# tang1.net
KiCad netlist of a schematic drawn in Altium Designer
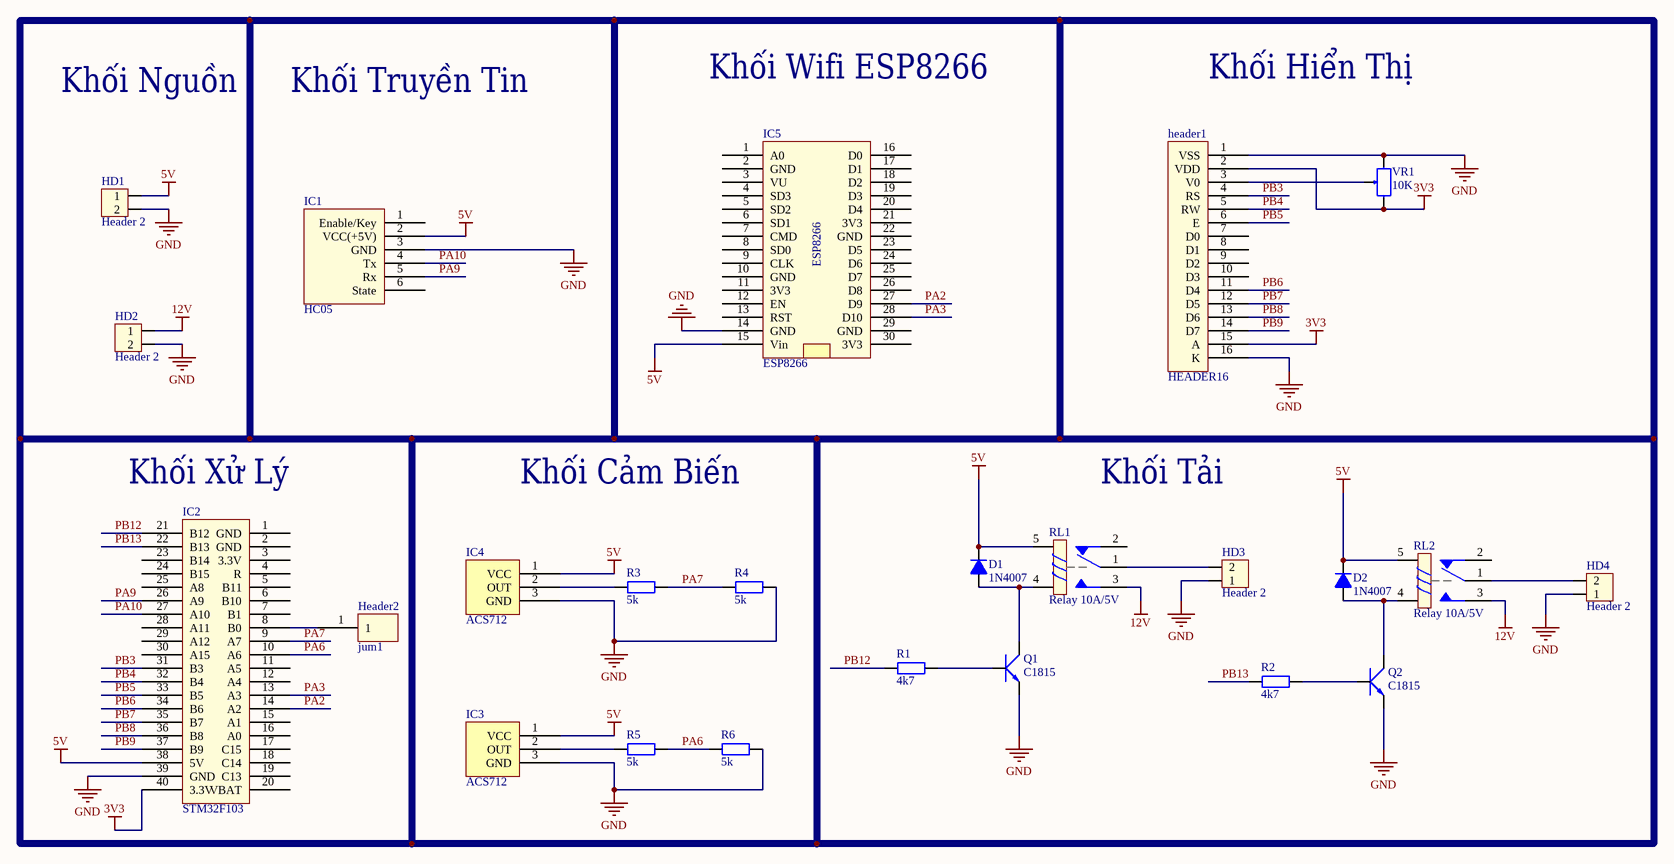
[diagram p0: tang1.SchDoc]

(export (version "E")
  (design (tool "Eeschema 10.0.6"))
  (components
    (comp (ref "D1")
      (value "1N4007")
      (footprint "D1A")
      (description "Diode 1A")
      (libsource (lib "syhaunguyen") (part "D1A"))
    )
    (comp (ref "D2")
      (value "1N4007")
      (footprint "D1A")
      (description "Diode 1A")
      (libsource (lib "syhaunguyen") (part "D1A"))
    )
    (comp (ref "HD1")
      (value "Header 2")
      (footprint "HED2")
      (description "Header 2 (Green)")
      (libsource (lib "") (part "Hed2_1"))
    )
    (comp (ref "HD2")
      (value "Header 2")
      (footprint "HED2")
      (description "Header 2 (Green)")
      (libsource (lib "") (part "Hed2_1"))
    )
    (comp (ref "HD3")
      (value "Header 2")
      (footprint "HED2")
      (description "Header 2 (Green)")
      (libsource (lib "syhaunguyen") (part "Hed2"))
    )
    (comp (ref "HD4")
      (value "Header 2")
      (footprint "HED2")
      (description "Header 2 (Green)")
      (libsource (lib "syhaunguyen") (part "Hed2"))
    )
    (comp (ref "header1")
      (value "HEADER16")
      (footprint "header16_pin")
      (libsource (lib "header16") (part "HEADER16"))
    )
    (comp (ref "Header2") (value "jum1") (footprint "PCBComponent_1") (libsource (lib "jum1") (part "jum1")))
    (comp (ref "IC1") (value "HC05") (footprint "HC05_Pin") (libsource (lib "hc05") (part "HC05")))
    (comp (ref "IC2")
      (value "STM32F103")
      (footprint "STM32")
      (libsource (lib "STM32F103") (part "STM32F103"))
    )
    (comp (ref "IC3")
      (value "ACS712")
      (footprint "ACS712:PCBComponent_1")
      (libsource (lib "ACS712") (part "ACS712"))
    )
    (comp (ref "IC4")
      (value "ACS712")
      (footprint "ACS712:PCBComponent_1")
      (libsource (lib "ACS712") (part "ACS712"))
    )
    (comp (ref "IC5")
      (value "ESP8266")
      (footprint "ESP8266 V2")
      (libsource (lib "ESP8266_V2") (part "ESP8266_V2"))
    )
    (comp (ref "Q1")
      (value "C1815")
      (footprint "QTO-92")
      (description "NPN 600mW, ECB")
      (libsource (lib "syhaunguyen") (part "C1815"))
    )
    (comp (ref "Q2")
      (value "C1815")
      (footprint "QTO-92")
      (description "NPN 600mW, ECB")
      (libsource (lib "syhaunguyen") (part "C1815"))
    )
    (comp (ref "R1")
      (value "4k7")
      (footprint "R1/4W")
      (description "Resistor 1/4W")
      (libsource (lib "syhaunguyen") (part "R1/4W"))
    )
    (comp (ref "R2")
      (value "4k7")
      (footprint "R1/4W")
      (description "Resistor 1/4W")
      (libsource (lib "syhaunguyen") (part "R1/4W"))
    )
    (comp (ref "R3")
      (value "5k")
      (footprint "R1/4W")
      (description "Resistor 1/4W")
      (libsource (lib "syhaunguyen") (part "R1/4W"))
    )
    (comp (ref "R4")
      (value "5k")
      (footprint "R1/4W")
      (description "Resistor 1/4W")
      (libsource (lib "syhaunguyen") (part "R1/4W"))
    )
    (comp (ref "R5")
      (value "5k")
      (footprint "R1/4W")
      (description "Resistor 1/4W")
      (libsource (lib "syhaunguyen") (part "R1/4W"))
    )
    (comp (ref "R6")
      (value "5k")
      (footprint "R1/4W")
      (description "Resistor 1/4W")
      (libsource (lib "syhaunguyen") (part "R1/4W"))
    )
    (comp (ref "RL1")
      (value "Relay 10A/5V")
      (footprint "RL_SPDT_10A")
      (description "Relay SPDT,10A - 12VDC 5 Pin")
      (libsource (lib "syhaunguyen") (part "Relay 1"))
    )
    (comp (ref "RL2")
      (value "Relay 10A/5V")
      (footprint "RL_SPDT_10A")
      (description "Relay SPDT,10A - 12VDC 5 Pin")
      (libsource (lib "syhaunguyen") (part "Relay 1"))
    )
    (comp (ref "VR1")
      (value "10K")
      (footprint "VR")
      (description "Var Resistor")
      (libsource (lib "syhaunguyen") (part "VR"))
    )
  )
  (nets
    (net (code "1") (name "/PA2") (class "Default")
      (node (ref "IC2") (pin "14") (pinfunction "A2_14") (pintype "passive"))
      (node (ref "IC5") (pin "27") (pinfunction "D9_27") (pintype "passive"))
    )
    (net (code "2") (name "/PA3") (class "Default")
      (node (ref "IC2") (pin "13") (pinfunction "A3_13") (pintype "passive"))
      (node (ref "IC5") (pin "28") (pinfunction "D10_28") (pintype "passive"))
    )
    (net (code "3") (name "/PA6") (class "Default")
      (node (ref "IC2") (pin "10") (pinfunction "A6_10") (pintype "passive"))
      (node (ref "R5") (pin "2") (pinfunction "2_2") (pintype "passive"))
      (node (ref "R6") (pin "1") (pinfunction "1_1") (pintype "passive"))
    )
    (net (code "4") (name "/PA7") (class "Default")
      (node (ref "IC2") (pin "9") (pinfunction "A7_9") (pintype "passive"))
      (node (ref "R3") (pin "2") (pinfunction "2_2") (pintype "passive"))
      (node (ref "R4") (pin "1") (pinfunction "1_1") (pintype "passive"))
    )
    (net (code "5") (name "/PA9") (class "Default")
      (node (ref "IC1") (pin "5") (pinfunction "Rx_5") (pintype "passive"))
      (node (ref "IC2") (pin "26") (pinfunction "A9_26") (pintype "passive"))
    )
    (net (code "6") (name "/PA10") (class "Default")
      (node (ref "IC1") (pin "4") (pinfunction "Tx_4") (pintype "passive"))
      (node (ref "IC2") (pin "27") (pinfunction "A10_27") (pintype "passive"))
    )
    (net (code "7") (name "/PB3") (class "Default")
      (node (ref "IC2") (pin "31") (pinfunction "B3_31") (pintype "passive"))
      (node (ref "header1") (pin "4") (pinfunction "RS_4") (pintype "passive"))
    )
    (net (code "8") (name "/PB4") (class "Default")
      (node (ref "IC2") (pin "32") (pinfunction "B4_32") (pintype "passive"))
      (node (ref "header1") (pin "5") (pinfunction "RW_5") (pintype "passive"))
    )
    (net (code "9") (name "/PB5") (class "Default")
      (node (ref "IC2") (pin "33") (pinfunction "B5_33") (pintype "passive"))
      (node (ref "header1") (pin "6") (pinfunction "E_6") (pintype "passive"))
    )
    (net (code "10") (name "/PB6") (class "Default")
      (node (ref "IC2") (pin "34") (pinfunction "B6_34") (pintype "passive"))
      (node (ref "header1") (pin "11") (pinfunction "D4_11") (pintype "passive"))
    )
    (net (code "11") (name "/PB7") (class "Default")
      (node (ref "IC2") (pin "35") (pinfunction "B7_35") (pintype "passive"))
      (node (ref "header1") (pin "12") (pinfunction "D5_12") (pintype "passive"))
    )
    (net (code "12") (name "/PB8") (class "Default")
      (node (ref "IC2") (pin "36") (pinfunction "B8_36") (pintype "passive"))
      (node (ref "header1") (pin "13") (pinfunction "D6_13") (pintype "passive"))
    )
    (net (code "13") (name "/PB9") (class "Default")
      (node (ref "IC2") (pin "37") (pinfunction "B9_37") (pintype "passive"))
      (node (ref "header1") (pin "14") (pinfunction "D7_14") (pintype "passive"))
    )
    (net (code "14") (name "/PB12") (class "Default")
      (node (ref "IC2") (pin "21") (pinfunction "B12_21") (pintype "passive"))
      (node (ref "R1") (pin "1") (pinfunction "1_1") (pintype "passive"))
    )
    (net (code "15") (name "/PB13") (class "Default")
      (node (ref "IC2") (pin "22") (pinfunction "B13_22") (pintype "passive"))
      (node (ref "R2") (pin "1") (pinfunction "1_1") (pintype "passive"))
    )
    (net (code "16") (name "3V3") (class "Default")
      (node (ref "IC2") (pin "40") (pinfunction "3.3V_40") (pintype "passive"))
      (node (ref "VR1") (pin "1") (pinfunction "1_1") (pintype "passive"))
      (node (ref "header1") (pin "15") (pinfunction "A_15") (pintype "passive"))
      (node (ref "header1") (pin "2") (pinfunction "VDD_2") (pintype "passive"))
    )
    (net (code "17") (name "5V") (class "Default")
      (node (ref "D1") (pin "2") (pinfunction "K_2") (pintype "passive"))
      (node (ref "D2") (pin "2") (pinfunction "K_2") (pintype "passive"))
      (node (ref "HD1") (pin "1") (pinfunction "1_1") (pintype "passive"))
      (node (ref "IC1") (pin "2") (pinfunction "VCC(+5V)_2") (pintype "passive"))
      (node (ref "IC2") (pin "38") (pinfunction "5V_38") (pintype "passive"))
      (node (ref "IC3") (pin "1") (pinfunction "VCC_1") (pintype "passive"))
      (node (ref "IC4") (pin "1") (pinfunction "VCC_1") (pintype "passive"))
      (node (ref "IC5") (pin "15") (pinfunction "Vin_15") (pintype "passive"))
      (node (ref "RL1") (pin "5") (pinfunction "5_5") (pintype "passive"))
      (node (ref "RL2") (pin "5") (pinfunction "5_5") (pintype "passive"))
    )
    (net (code "18") (name "12V") (class "Default")
      (node (ref "HD2") (pin "1") (pinfunction "1_1") (pintype "passive"))
      (node (ref "RL1") (pin "3") (pinfunction "3_3") (pintype "passive"))
      (node (ref "RL2") (pin "3") (pinfunction "3_3") (pintype "passive"))
    )
    (net (code "19") (name "GND") (class "Default")
      (node (ref "HD1") (pin "2") (pinfunction "2_2") (pintype "passive"))
      (node (ref "HD2") (pin "2") (pinfunction "2_2") (pintype "passive"))
      (node (ref "HD3") (pin "1") (pinfunction "1_1") (pintype "passive"))
      (node (ref "HD4") (pin "1") (pinfunction "1_1") (pintype "passive"))
      (node (ref "IC1") (pin "3") (pinfunction "GND_3") (pintype "passive"))
      (node (ref "IC2") (pin "39") (pinfunction "GND_39") (pintype "passive"))
      (node (ref "IC3") (pin "3") (pinfunction "GND_3") (pintype "passive"))
      (node (ref "IC4") (pin "3") (pinfunction "GND_3") (pintype "passive"))
      (node (ref "IC5") (pin "14") (pinfunction "GND_14") (pintype "passive"))
      (node (ref "Q1") (pin "1") (pinfunction "E_1") (pintype "passive"))
      (node (ref "Q2") (pin "1") (pinfunction "E_1") (pintype "passive"))
      (node (ref "R4") (pin "2") (pinfunction "2_2") (pintype "passive"))
      (node (ref "R6") (pin "2") (pinfunction "2_2") (pintype "passive"))
      (node (ref "VR1") (pin "3") (pinfunction "3_3") (pintype "passive"))
      (node (ref "header1") (pin "1") (pinfunction "VSS_1") (pintype "passive"))
      (node (ref "header1") (pin "16") (pinfunction "K_16") (pintype "passive"))
    )
    (net (code "20") (name "Net-(D1-A)") (class "Default")
      (node (ref "D1") (pin "1") (pinfunction "A_1") (pintype "passive"))
      (node (ref "Q1") (pin "2") (pinfunction "C_2") (pintype "passive"))
      (node (ref "RL1") (pin "4") (pinfunction "4_4") (pintype "passive"))
    )
    (net (code "21") (name "Net-(D2-A)") (class "Default")
      (node (ref "D2") (pin "1") (pinfunction "A_1") (pintype "passive"))
      (node (ref "Q2") (pin "2") (pinfunction "C_2") (pintype "passive"))
      (node (ref "RL2") (pin "4") (pinfunction "4_4") (pintype "passive"))
    )
    (net (code "22") (name "Net-(HD3-Pad2)") (class "Default")
      (node (ref "HD3") (pin "2") (pinfunction "2_2") (pintype "passive"))
      (node (ref "RL1") (pin "1") (pinfunction "1_1") (pintype "passive"))
    )
    (net (code "23") (name "Net-(HD4-Pad2)") (class "Default")
      (node (ref "HD4") (pin "2") (pinfunction "2_2") (pintype "passive"))
      (node (ref "RL2") (pin "1") (pinfunction "1_1") (pintype "passive"))
    )
    (net (code "24") (name "Net-(IC2-B0)") (class "Default")
      (node (ref "Header2") (pin "1") (pinfunction "1_1") (pintype "passive"))
      (node (ref "IC2") (pin "8") (pinfunction "B0_8") (pintype "passive"))
    )
    (net (code "25") (name "Net-(IC3-OUT)") (class "Default")
      (node (ref "IC3") (pin "2") (pinfunction "OUT_2") (pintype "passive"))
      (node (ref "R5") (pin "1") (pinfunction "1_1") (pintype "passive"))
    )
    (net (code "26") (name "Net-(IC4-OUT)") (class "Default")
      (node (ref "IC4") (pin "2") (pinfunction "OUT_2") (pintype "passive"))
      (node (ref "R3") (pin "1") (pinfunction "1_1") (pintype "passive"))
    )
    (net (code "27") (name "Net-(Q1-B)") (class "Default")
      (node (ref "Q1") (pin "3") (pinfunction "B_3") (pintype "passive"))
      (node (ref "R1") (pin "2") (pinfunction "2_2") (pintype "passive"))
    )
    (net (code "28") (name "Net-(Q2-B)") (class "Default")
      (node (ref "Q2") (pin "3") (pinfunction "B_3") (pintype "passive"))
      (node (ref "R2") (pin "2") (pinfunction "2_2") (pintype "passive"))
    )
    (net (code "29") (name "Net-(header1-V0)") (class "Default")
      (node (ref "VR1") (pin "2") (pinfunction "2_2") (pintype "passive"))
      (node (ref "header1") (pin "3") (pinfunction "V0_3") (pintype "passive"))
    )
    (net (code "30") (name "unconnected-(IC1-Enable{slash}Key-Pad1)") (class "Default")
      (node (ref "IC1") (pin "1") (pinfunction "Enable/Key_1") (pintype "passive"))
    )
    (net (code "31") (name "unconnected-(IC1-State-Pad6)") (class "Default")
      (node (ref "IC1") (pin "6") (pinfunction "State_6") (pintype "passive"))
    )
    (net (code "32") (name "unconnected-(IC2-3.3V-Pad3)") (class "Default")
      (node (ref "IC2") (pin "3") (pinfunction "3.3V_3") (pintype "passive"))
    )
    (net (code "33") (name "unconnected-(IC2-A0-Pad16)") (class "Default")
      (node (ref "IC2") (pin "16") (pinfunction "A0_16") (pintype "passive"))
    )
    (net (code "34") (name "unconnected-(IC2-A1-Pad15)") (class "Default")
      (node (ref "IC2") (pin "15") (pinfunction "A1_15") (pintype "passive"))
    )
    (net (code "35") (name "unconnected-(IC2-A4-Pad12)") (class "Default")
      (node (ref "IC2") (pin "12") (pinfunction "A4_12") (pintype "passive"))
    )
    (net (code "36") (name "unconnected-(IC2-A5-Pad11)") (class "Default")
      (node (ref "IC2") (pin "11") (pinfunction "A5_11") (pintype "passive"))
    )
    (net (code "37") (name "unconnected-(IC2-A8-Pad25)") (class "Default")
      (node (ref "IC2") (pin "25") (pinfunction "A8_25") (pintype "passive"))
    )
    (net (code "38") (name "unconnected-(IC2-A11-Pad28)") (class "Default")
      (node (ref "IC2") (pin "28") (pinfunction "A11_28") (pintype "passive"))
    )
    (net (code "39") (name "unconnected-(IC2-A12-Pad29)") (class "Default")
      (node (ref "IC2") (pin "29") (pinfunction "A12_29") (pintype "passive"))
    )
    (net (code "40") (name "unconnected-(IC2-A15-Pad30)") (class "Default")
      (node (ref "IC2") (pin "30") (pinfunction "A15_30") (pintype "passive"))
    )
    (net (code "41") (name "unconnected-(IC2-B1-Pad7)") (class "Default")
      (node (ref "IC2") (pin "7") (pinfunction "B1_7") (pintype "passive"))
    )
    (net (code "42") (name "unconnected-(IC2-B10-Pad6)") (class "Default")
      (node (ref "IC2") (pin "6") (pinfunction "B10_6") (pintype "passive"))
    )
    (net (code "43") (name "unconnected-(IC2-B11-Pad5)") (class "Default")
      (node (ref "IC2") (pin "5") (pinfunction "B11_5") (pintype "passive"))
    )
    (net (code "44") (name "unconnected-(IC2-B14-Pad23)") (class "Default")
      (node (ref "IC2") (pin "23") (pinfunction "B14_23") (pintype "passive"))
    )
    (net (code "45") (name "unconnected-(IC2-B15-Pad24)") (class "Default")
      (node (ref "IC2") (pin "24") (pinfunction "B15_24") (pintype "passive"))
    )
    (net (code "46") (name "unconnected-(IC2-C13-Pad19)") (class "Default")
      (node (ref "IC2") (pin "19") (pinfunction "C13_19") (pintype "passive"))
    )
    (net (code "47") (name "unconnected-(IC2-C14-Pad18)") (class "Default")
      (node (ref "IC2") (pin "18") (pinfunction "C14_18") (pintype "passive"))
    )
    (net (code "48") (name "unconnected-(IC2-C15-Pad17)") (class "Default")
      (node (ref "IC2") (pin "17") (pinfunction "C15_17") (pintype "passive"))
    )
    (net (code "49") (name "unconnected-(IC2-GND-Pad1)") (class "Default")
      (node (ref "IC2") (pin "1") (pinfunction "GND_1") (pintype "passive"))
    )
    (net (code "50") (name "unconnected-(IC2-GND-Pad2)") (class "Default")
      (node (ref "IC2") (pin "2") (pinfunction "GND_2") (pintype "passive"))
    )
    (net (code "51") (name "unconnected-(IC2-R-Pad4)") (class "Default")
      (node (ref "IC2") (pin "4") (pinfunction "R_4") (pintype "passive"))
    )
    (net (code "52") (name "unconnected-(IC2-VBAT-Pad20)") (class "Default")
      (node (ref "IC2") (pin "20") (pinfunction "VBAT_20") (pintype "passive"))
    )
    (net (code "53") (name "unconnected-(IC5-3V3-Pad11)") (class "Default")
      (node (ref "IC5") (pin "11") (pinfunction "3V3_11") (pintype "passive"))
    )
    (net (code "54") (name "unconnected-(IC5-3V3-Pad21)") (class "Default")
      (node (ref "IC5") (pin "21") (pinfunction "3V3_21") (pintype "passive"))
    )
    (net (code "55") (name "unconnected-(IC5-3V3-Pad30)") (class "Default")
      (node (ref "IC5") (pin "30") (pinfunction "3V3_30") (pintype "passive"))
    )
    (net (code "56") (name "unconnected-(IC5-A0-Pad1)") (class "Default")
      (node (ref "IC5") (pin "1") (pinfunction "A0_1") (pintype "passive"))
    )
    (net (code "57") (name "unconnected-(IC5-CLK-Pad9)") (class "Default")
      (node (ref "IC5") (pin "9") (pinfunction "CLK_9") (pintype "passive"))
    )
    (net (code "58") (name "unconnected-(IC5-CMD-Pad7)") (class "Default")
      (node (ref "IC5") (pin "7") (pinfunction "CMD_7") (pintype "passive"))
    )
    (net (code "59") (name "unconnected-(IC5-D0-Pad16)") (class "Default")
      (node (ref "IC5") (pin "16") (pinfunction "D0_16") (pintype "passive"))
    )
    (net (code "60") (name "unconnected-(IC5-D1-Pad17)") (class "Default")
      (node (ref "IC5") (pin "17") (pinfunction "D1_17") (pintype "passive"))
    )
    (net (code "61") (name "unconnected-(IC5-D2-Pad18)") (class "Default")
      (node (ref "IC5") (pin "18") (pinfunction "D2_18") (pintype "passive"))
    )
    (net (code "62") (name "unconnected-(IC5-D3-Pad19)") (class "Default")
      (node (ref "IC5") (pin "19") (pinfunction "D3_19") (pintype "passive"))
    )
    (net (code "63") (name "unconnected-(IC5-D4-Pad20)") (class "Default")
      (node (ref "IC5") (pin "20") (pinfunction "D4_20") (pintype "passive"))
    )
    (net (code "64") (name "unconnected-(IC5-D5-Pad23)") (class "Default")
      (node (ref "IC5") (pin "23") (pinfunction "D5_23") (pintype "passive"))
    )
    (net (code "65") (name "unconnected-(IC5-D6-Pad24)") (class "Default")
      (node (ref "IC5") (pin "24") (pinfunction "D6_24") (pintype "passive"))
    )
    (net (code "66") (name "unconnected-(IC5-D7-Pad25)") (class "Default")
      (node (ref "IC5") (pin "25") (pinfunction "D7_25") (pintype "passive"))
    )
    (net (code "67") (name "unconnected-(IC5-D8-Pad26)") (class "Default")
      (node (ref "IC5") (pin "26") (pinfunction "D8_26") (pintype "passive"))
    )
    (net (code "68") (name "unconnected-(IC5-EN-Pad12)") (class "Default")
      (node (ref "IC5") (pin "12") (pinfunction "EN_12") (pintype "passive"))
    )
    (net (code "69") (name "unconnected-(IC5-GND-Pad2)") (class "Default")
      (node (ref "IC5") (pin "2") (pinfunction "GND_2") (pintype "passive"))
    )
    (net (code "70") (name "unconnected-(IC5-GND-Pad10)") (class "Default")
      (node (ref "IC5") (pin "10") (pinfunction "GND_10") (pintype "passive"))
    )
    (net (code "71") (name "unconnected-(IC5-GND-Pad22)") (class "Default")
      (node (ref "IC5") (pin "22") (pinfunction "GND_22") (pintype "passive"))
    )
    (net (code "72") (name "unconnected-(IC5-GND-Pad29)") (class "Default")
      (node (ref "IC5") (pin "29") (pinfunction "GND_29") (pintype "passive"))
    )
    (net (code "73") (name "unconnected-(IC5-RST-Pad13)") (class "Default")
      (node (ref "IC5") (pin "13") (pinfunction "RST_13") (pintype "passive"))
    )
    (net (code "74") (name "unconnected-(IC5-SD0-Pad8)") (class "Default")
      (node (ref "IC5") (pin "8") (pinfunction "SD0_8") (pintype "passive"))
    )
    (net (code "75") (name "unconnected-(IC5-SD1-Pad6)") (class "Default")
      (node (ref "IC5") (pin "6") (pinfunction "SD1_6") (pintype "passive"))
    )
    (net (code "76") (name "unconnected-(IC5-SD2-Pad5)") (class "Default")
      (node (ref "IC5") (pin "5") (pinfunction "SD2_5") (pintype "passive"))
    )
    (net (code "77") (name "unconnected-(IC5-SD3-Pad4)") (class "Default")
      (node (ref "IC5") (pin "4") (pinfunction "SD3_4") (pintype "passive"))
    )
    (net (code "78") (name "unconnected-(IC5-VU-Pad3)") (class "Default")
      (node (ref "IC5") (pin "3") (pinfunction "VU_3") (pintype "passive"))
    )
    (net (code "79") (name "unconnected-(RL1-Pad2)") (class "Default")
      (node (ref "RL1") (pin "2") (pinfunction "2_2") (pintype "passive"))
    )
    (net (code "80") (name "unconnected-(RL2-Pad2)") (class "Default")
      (node (ref "RL2") (pin "2") (pinfunction "2_2") (pintype "passive"))
    )
    (net (code "81") (name "unconnected-(header1-D0-Pad7)") (class "Default")
      (node (ref "header1") (pin "7") (pinfunction "D0_7") (pintype "passive"))
    )
    (net (code "82") (name "unconnected-(header1-D1-Pad8)") (class "Default")
      (node (ref "header1") (pin "8") (pinfunction "D1_8") (pintype "passive"))
    )
    (net (code "83") (name "unconnected-(header1-D2-Pad9)") (class "Default")
      (node (ref "header1") (pin "9") (pinfunction "D2_9") (pintype "passive"))
    )
    (net (code "84") (name "unconnected-(header1-D3-Pad10)") (class "Default")
      (node (ref "header1") (pin "10") (pinfunction "D3_10") (pintype "passive"))
    )
  )
)
